# OpenLightingController.net
KiCad netlist of a schematic drawn in EasyEDA Pro
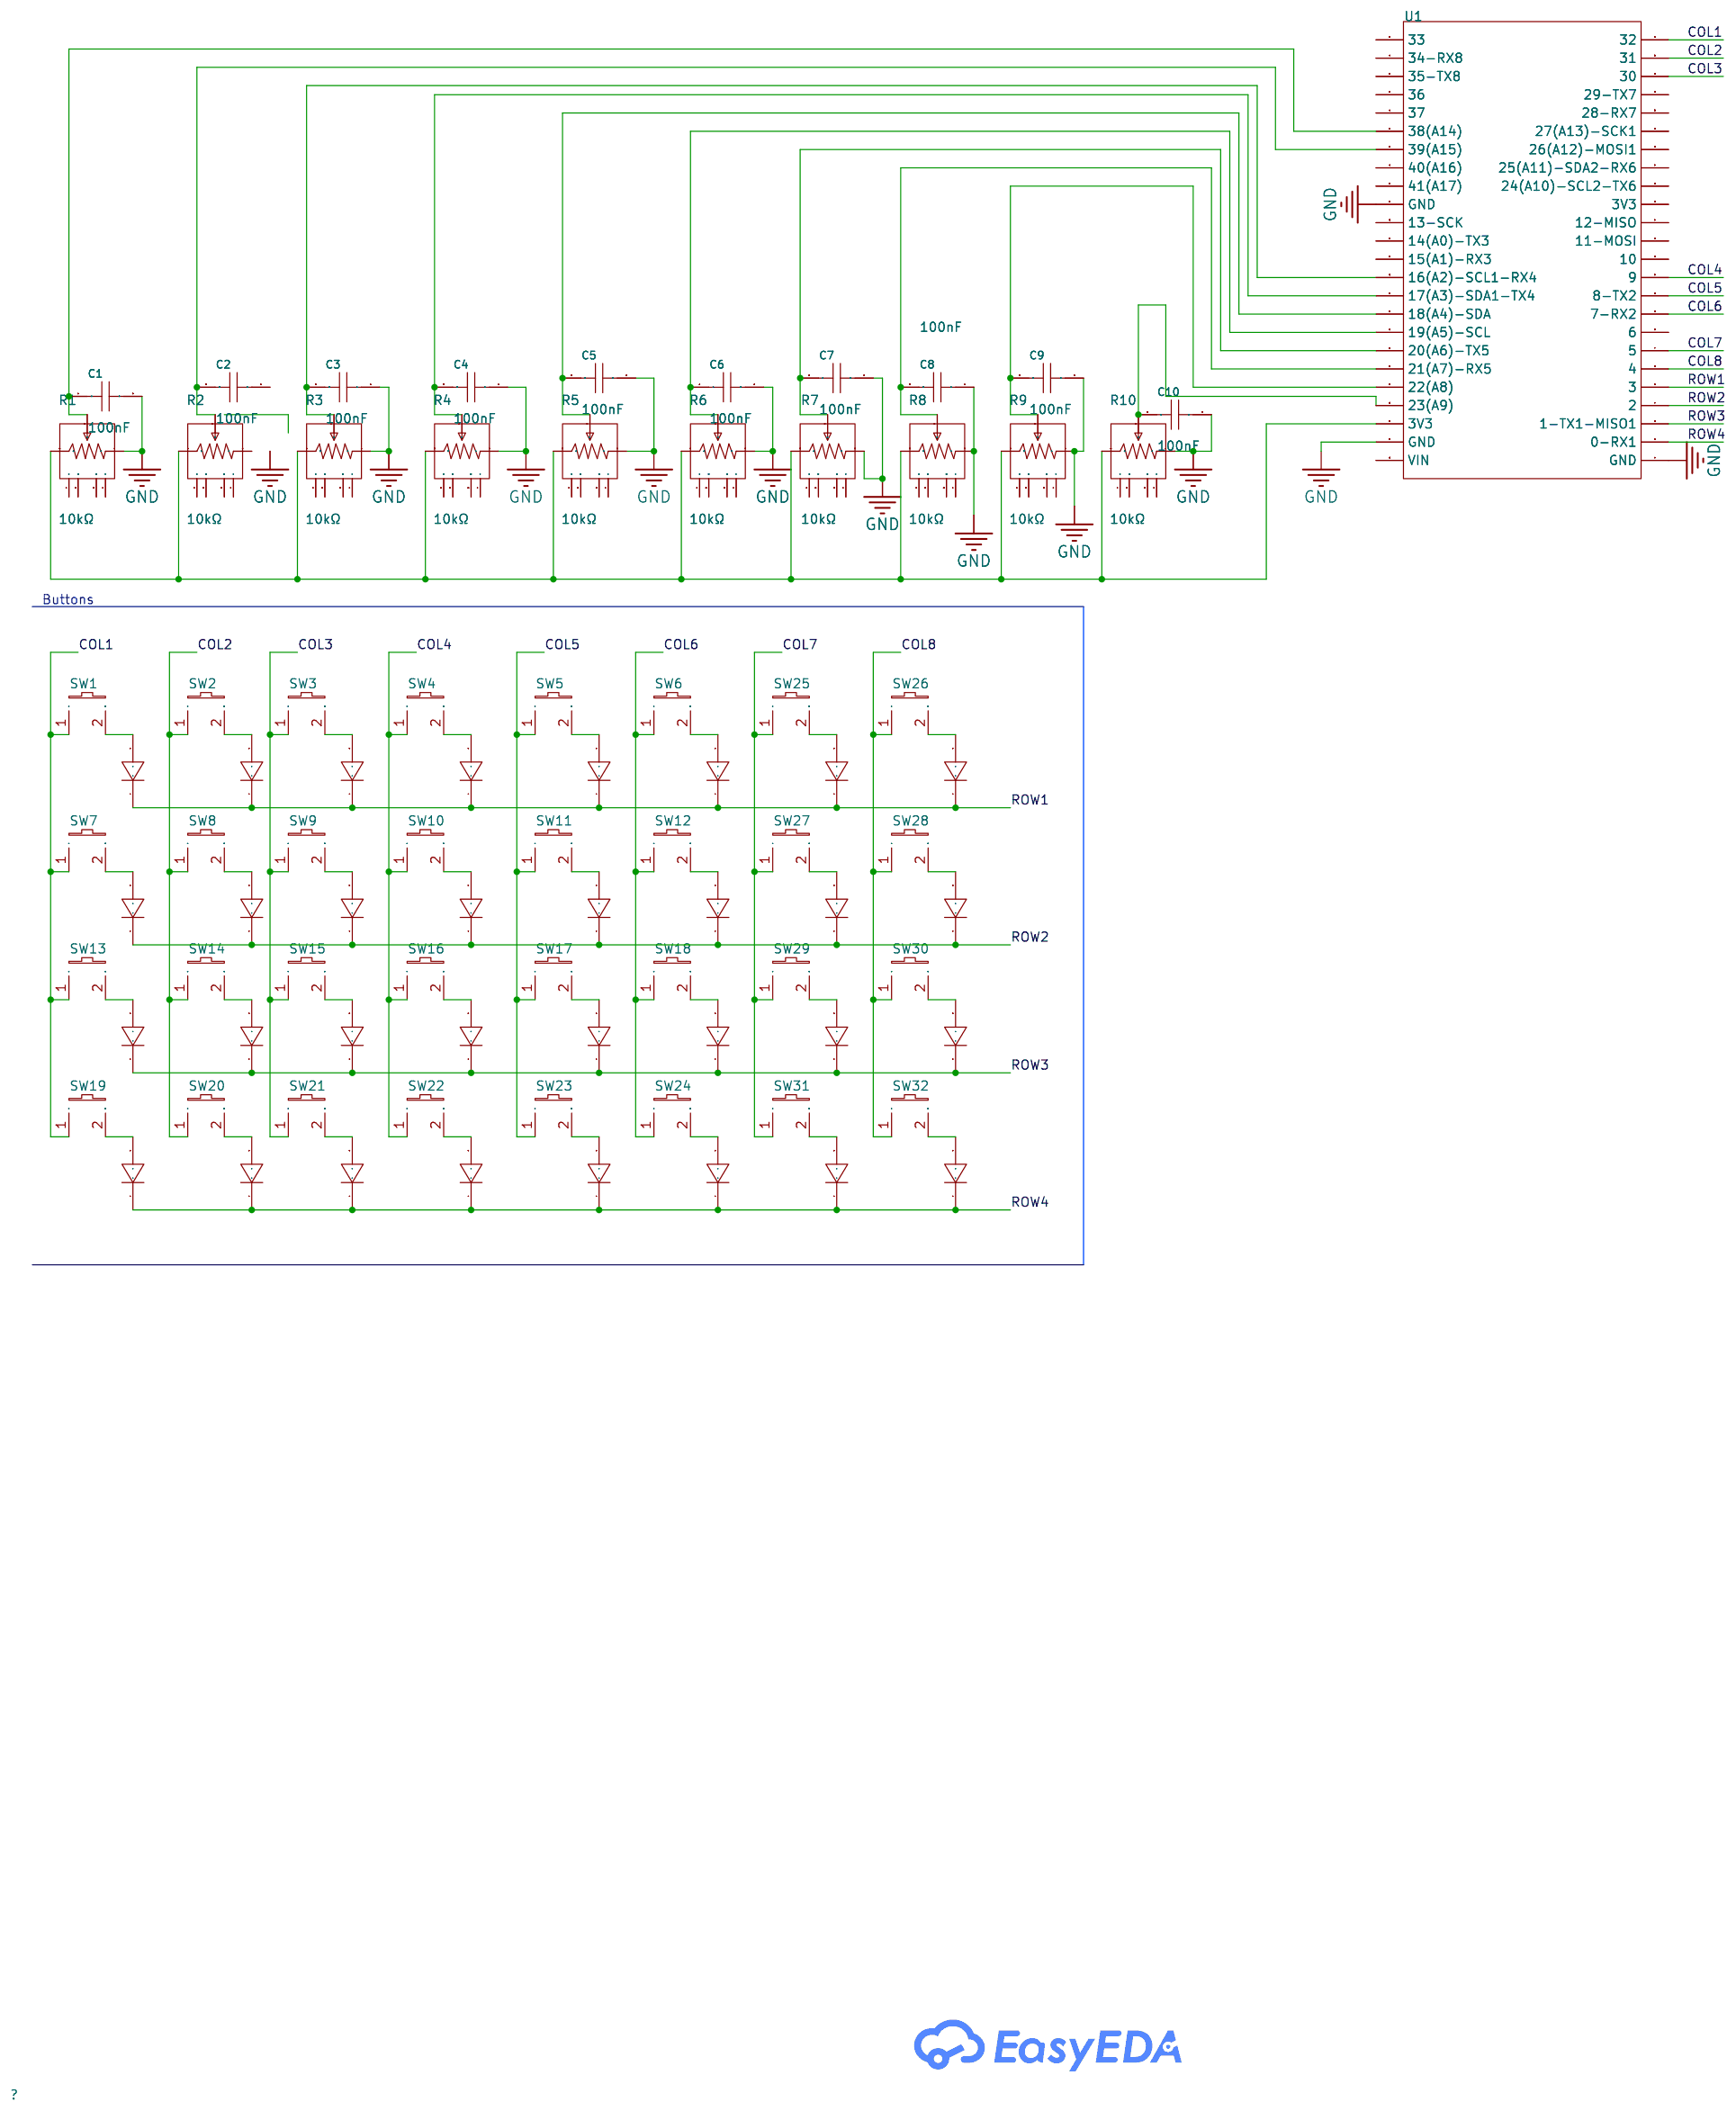
[diagram p0: schematic sheet]

(export (version "E")
  (design (tool "Eeschema 10.0.6"))
  (components
    (comp (ref "C1")
      (value "100nF")
      (fields
        (field (name "Manufacturer Part") "CC1H104ZA1ED3F5P1100")
        (field (name "Manufacturer") "Dersonic(德尔创)")
      )
      (libsource (lib "easyedapro") (part "CL10B104KB8NNNC"))
    )
    (comp (ref "C2")
      (value "100nF")
      (fields
        (field (name "Manufacturer Part") "CC1H104ZA1ED3F5P1100")
        (field (name "Manufacturer") "Dersonic(德尔创)")
      )
      (libsource (lib "easyedapro") (part "CL10B104KB8NNNC"))
    )
    (comp (ref "C3")
      (value "100nF")
      (fields
        (field (name "Manufacturer Part") "CC1H104ZA1ED3F5P1100")
        (field (name "Manufacturer") "Dersonic(德尔创)")
      )
      (libsource (lib "easyedapro") (part "CL10B104KB8NNNC"))
    )
    (comp (ref "C4")
      (value "100nF")
      (fields
        (field (name "Manufacturer Part") "CC1H104ZA1ED3F5P1100")
        (field (name "Manufacturer") "Dersonic(德尔创)")
      )
      (libsource (lib "easyedapro") (part "CL10B104KB8NNNC"))
    )
    (comp (ref "C5")
      (value "100nF")
      (fields
        (field (name "Manufacturer Part") "CC1H104ZA1ED3F5P1100")
        (field (name "Manufacturer") "Dersonic(德尔创)")
      )
      (libsource (lib "easyedapro") (part "CL10B104KB8NNNC"))
    )
    (comp (ref "C6")
      (value "100nF")
      (fields
        (field (name "Manufacturer Part") "CC1H104ZA1ED3F5P1100")
        (field (name "Manufacturer") "Dersonic(德尔创)")
      )
      (libsource (lib "easyedapro") (part "CL10B104KB8NNNC"))
    )
    (comp (ref "C7")
      (value "100nF")
      (fields
        (field (name "Manufacturer Part") "CC1H104ZA1ED3F5P1100")
        (field (name "Manufacturer") "Dersonic(德尔创)")
      )
      (libsource (lib "easyedapro") (part "CL10B104KB8NNNC"))
    )
    (comp (ref "C8")
      (value "100nF")
      (fields
        (field (name "Manufacturer Part") "CC1H104ZA1ED3F5P1100")
        (field (name "Manufacturer") "Dersonic(德尔创)")
      )
      (libsource (lib "easyedapro") (part "CL10B104KB8NNNC"))
    )
    (comp (ref "C9")
      (value "100nF")
      (fields
        (field (name "Manufacturer Part") "CC1H104ZA1ED3F5P1100")
        (field (name "Manufacturer") "Dersonic(德尔创)")
      )
      (libsource (lib "easyedapro") (part "CL10B104KB8NNNC"))
    )
    (comp (ref "C10")
      (value "100nF")
      (fields
        (field (name "Manufacturer Part") "CC1H104ZA1ED3F5P1100")
        (field (name "Manufacturer") "Dersonic(德尔创)")
      )
      (libsource (lib "easyedapro") (part "CL10B104KB8NNNC"))
    )
    (comp (ref "D1")
      (value "1N4148")
      (fields (field (name "Manufacturer") "onsemi(安森美)"))
      (libsource (lib "easyedapro") (part "1N4148W_C81598"))
    )
    (comp (ref "D2")
      (value "1N4148")
      (fields (field (name "Manufacturer") "onsemi(安森美)"))
      (libsource (lib "easyedapro") (part "1N4148W_C81598"))
    )
    (comp (ref "D3")
      (value "1N4148")
      (fields (field (name "Manufacturer") "onsemi(安森美)"))
      (libsource (lib "easyedapro") (part "1N4148W_C81598"))
    )
    (comp (ref "D4")
      (value "1N4148")
      (fields (field (name "Manufacturer") "onsemi(安森美)"))
      (libsource (lib "easyedapro") (part "1N4148W_C81598"))
    )
    (comp (ref "D5")
      (value "1N4148")
      (fields (field (name "Manufacturer") "onsemi(安森美)"))
      (libsource (lib "easyedapro") (part "1N4148W_C81598"))
    )
    (comp (ref "D6")
      (value "1N4148")
      (fields (field (name "Manufacturer") "onsemi(安森美)"))
      (libsource (lib "easyedapro") (part "1N4148W_C81598"))
    )
    (comp (ref "D7")
      (value "1N4148")
      (fields (field (name "Manufacturer") "onsemi(安森美)"))
      (libsource (lib "easyedapro") (part "1N4148W_C81598"))
    )
    (comp (ref "D8")
      (value "1N4148")
      (fields (field (name "Manufacturer") "onsemi(安森美)"))
      (libsource (lib "easyedapro") (part "1N4148W_C81598"))
    )
    (comp (ref "D9")
      (value "1N4148")
      (fields (field (name "Manufacturer") "onsemi(安森美)"))
      (libsource (lib "easyedapro") (part "1N4148W_C81598"))
    )
    (comp (ref "D10")
      (value "1N4148")
      (fields (field (name "Manufacturer") "onsemi(安森美)"))
      (libsource (lib "easyedapro") (part "1N4148W_C81598"))
    )
    (comp (ref "D11")
      (value "1N4148")
      (fields (field (name "Manufacturer") "onsemi(安森美)"))
      (libsource (lib "easyedapro") (part "1N4148W_C81598"))
    )
    (comp (ref "D12")
      (value "1N4148")
      (fields (field (name "Manufacturer") "onsemi(安森美)"))
      (libsource (lib "easyedapro") (part "1N4148W_C81598"))
    )
    (comp (ref "D13")
      (value "1N4148")
      (fields (field (name "Manufacturer") "onsemi(安森美)"))
      (libsource (lib "easyedapro") (part "1N4148W_C81598"))
    )
    (comp (ref "D14")
      (value "1N4148")
      (fields (field (name "Manufacturer") "onsemi(安森美)"))
      (libsource (lib "easyedapro") (part "1N4148W_C81598"))
    )
    (comp (ref "D15")
      (value "1N4148")
      (fields (field (name "Manufacturer") "onsemi(安森美)"))
      (libsource (lib "easyedapro") (part "1N4148W_C81598"))
    )
    (comp (ref "D16")
      (value "1N4148")
      (fields (field (name "Manufacturer") "onsemi(安森美)"))
      (libsource (lib "easyedapro") (part "1N4148W_C81598"))
    )
    (comp (ref "D17")
      (value "1N4148")
      (fields (field (name "Manufacturer") "onsemi(安森美)"))
      (libsource (lib "easyedapro") (part "1N4148W_C81598"))
    )
    (comp (ref "D18")
      (value "1N4148")
      (fields (field (name "Manufacturer") "onsemi(安森美)"))
      (libsource (lib "easyedapro") (part "1N4148W_C81598"))
    )
    (comp (ref "D19")
      (value "1N4148")
      (fields (field (name "Manufacturer") "onsemi(安森美)"))
      (libsource (lib "easyedapro") (part "1N4148W_C81598"))
    )
    (comp (ref "D20")
      (value "1N4148")
      (fields (field (name "Manufacturer") "onsemi(安森美)"))
      (libsource (lib "easyedapro") (part "1N4148W_C81598"))
    )
    (comp (ref "D21")
      (value "1N4148")
      (fields (field (name "Manufacturer") "onsemi(安森美)"))
      (libsource (lib "easyedapro") (part "1N4148W_C81598"))
    )
    (comp (ref "D22")
      (value "1N4148")
      (fields (field (name "Manufacturer") "onsemi(安森美)"))
      (libsource (lib "easyedapro") (part "1N4148W_C81598"))
    )
    (comp (ref "D23")
      (value "1N4148")
      (fields (field (name "Manufacturer") "onsemi(安森美)"))
      (libsource (lib "easyedapro") (part "1N4148W_C81598"))
    )
    (comp (ref "D24")
      (value "1N4148")
      (fields (field (name "Manufacturer") "onsemi(安森美)"))
      (libsource (lib "easyedapro") (part "1N4148W_C81598"))
    )
    (comp (ref "D25")
      (value "1N4148")
      (fields (field (name "Manufacturer") "onsemi(安森美)"))
      (libsource (lib "easyedapro") (part "1N4148W_C81598"))
    )
    (comp (ref "D26")
      (value "1N4148")
      (fields (field (name "Manufacturer") "onsemi(安森美)"))
      (libsource (lib "easyedapro") (part "1N4148W_C81598"))
    )
    (comp (ref "D27")
      (value "1N4148")
      (fields (field (name "Manufacturer") "onsemi(安森美)"))
      (libsource (lib "easyedapro") (part "1N4148W_C81598"))
    )
    (comp (ref "D28")
      (value "1N4148")
      (fields (field (name "Manufacturer") "onsemi(安森美)"))
      (libsource (lib "easyedapro") (part "1N4148W_C81598"))
    )
    (comp (ref "D29")
      (value "1N4148")
      (fields (field (name "Manufacturer") "onsemi(安森美)"))
      (libsource (lib "easyedapro") (part "1N4148W_C81598"))
    )
    (comp (ref "D30")
      (value "1N4148")
      (fields (field (name "Manufacturer") "onsemi(安森美)"))
      (libsource (lib "easyedapro") (part "1N4148W_C81598"))
    )
    (comp (ref "D31")
      (value "1N4148")
      (fields (field (name "Manufacturer") "onsemi(安森美)"))
      (libsource (lib "easyedapro") (part "1N4148W_C81598"))
    )
    (comp (ref "D32")
      (value "1N4148")
      (fields (field (name "Manufacturer") "onsemi(安森美)"))
      (libsource (lib "easyedapro") (part "1N4148W_C81598"))
    )
    (comp (ref "R1")
      (value "10kΩ")
      (footprint "easyedapro:RES-ADJ-TH_PTA6043-2015DPB103")
      (description "Resistance:10kΩ Tolerance:±20% Tolerance:±20% Voltage Rating:200V Power(Watts):250mW")
      (fields (field (name "Manufacturer Part") "PTA6043-2015CPB103") (field (name "Manufacturer") "BOURNS"))
      (libsource (lib "easyedapro") (part "PTA6043-2015CPB103"))
    )
    (comp (ref "R2")
      (value "10kΩ")
      (footprint "easyedapro:RES-ADJ-TH_PTA6043-2015DPB103")
      (description "Resistance:10kΩ Tolerance:±20% Tolerance:±20% Voltage Rating:200V Power(Watts):250mW")
      (fields (field (name "Manufacturer Part") "PTA6043-2015CPB103") (field (name "Manufacturer") "BOURNS"))
      (libsource (lib "easyedapro") (part "PTA6043-2015CPB103"))
    )
    (comp (ref "R3")
      (value "10kΩ")
      (footprint "easyedapro:RES-ADJ-TH_PTA6043-2015DPB103")
      (description "Resistance:10kΩ Tolerance:±20% Tolerance:±20% Voltage Rating:200V Power(Watts):250mW")
      (fields (field (name "Manufacturer Part") "PTA6043-2015CPB103") (field (name "Manufacturer") "BOURNS"))
      (libsource (lib "easyedapro") (part "PTA6043-2015CPB103"))
    )
    (comp (ref "R4")
      (value "10kΩ")
      (footprint "easyedapro:RES-ADJ-TH_PTA6043-2015DPB103")
      (description "Resistance:10kΩ Tolerance:±20% Tolerance:±20% Voltage Rating:200V Power(Watts):250mW")
      (fields (field (name "Manufacturer Part") "PTA6043-2015CPB103") (field (name "Manufacturer") "BOURNS"))
      (libsource (lib "easyedapro") (part "PTA6043-2015CPB103"))
    )
    (comp (ref "R5")
      (value "10kΩ")
      (footprint "easyedapro:RES-ADJ-TH_PTA6043-2015DPB103")
      (description "Resistance:10kΩ Tolerance:±20% Tolerance:±20% Voltage Rating:200V Power(Watts):250mW")
      (fields (field (name "Manufacturer Part") "PTA6043-2015CPB103") (field (name "Manufacturer") "BOURNS"))
      (libsource (lib "easyedapro") (part "PTA6043-2015CPB103"))
    )
    (comp (ref "R6")
      (value "10kΩ")
      (footprint "easyedapro:RES-ADJ-TH_PTA6043-2015DPB103")
      (description "Resistance:10kΩ Tolerance:±20% Tolerance:±20% Voltage Rating:200V Power(Watts):250mW")
      (fields (field (name "Manufacturer Part") "PTA6043-2015CPB103") (field (name "Manufacturer") "BOURNS"))
      (libsource (lib "easyedapro") (part "PTA6043-2015CPB103"))
    )
    (comp (ref "R7")
      (value "10kΩ")
      (footprint "easyedapro:RES-ADJ-TH_PTA6043-2015DPB103")
      (description "Resistance:10kΩ Tolerance:±20% Tolerance:±20% Voltage Rating:200V Power(Watts):250mW")
      (fields (field (name "Manufacturer Part") "PTA6043-2015CPB103") (field (name "Manufacturer") "BOURNS"))
      (libsource (lib "easyedapro") (part "PTA6043-2015CPB103"))
    )
    (comp (ref "R8")
      (value "10kΩ")
      (footprint "easyedapro:RES-ADJ-TH_PTA6043-2015DPB103")
      (description "Resistance:10kΩ Tolerance:±20% Tolerance:±20% Voltage Rating:200V Power(Watts):250mW")
      (fields (field (name "Manufacturer Part") "PTA6043-2015CPB103") (field (name "Manufacturer") "BOURNS"))
      (libsource (lib "easyedapro") (part "PTA6043-2015CPB103"))
    )
    (comp (ref "R9")
      (value "10kΩ")
      (footprint "easyedapro:RES-ADJ-TH_PTA6043-2015DPB103")
      (description "Resistance:10kΩ Tolerance:±20% Tolerance:±20% Voltage Rating:200V Power(Watts):250mW")
      (fields (field (name "Manufacturer Part") "PTA6043-2015CPB103") (field (name "Manufacturer") "BOURNS"))
      (libsource (lib "easyedapro") (part "PTA6043-2015CPB103"))
    )
    (comp (ref "R10")
      (value "10kΩ")
      (footprint "easyedapro:RES-ADJ-TH_PTA6043-2015DPB103")
      (description "Resistance:10kΩ Tolerance:±20% Tolerance:±20% Voltage Rating:200V Power(Watts):250mW")
      (fields (field (name "Manufacturer Part") "PTA6043-2015CPB103") (field (name "Manufacturer") "BOURNS"))
      (libsource (lib "easyedapro") (part "PTA6043-2015CPB103"))
    )
    (comp (ref "SW1")
      (value "MX Switch")
      (footprint "easyedapro:SW-TH_MX1A-11NW")
      (fields (field (name "Manufacturer Part") "MX1A-11NW") (field (name "Manufacturer") "CHERRY"))
      (libsource (lib "easyedapro") (part "MX1A-11NW"))
    )
    (comp (ref "SW2")
      (value "MX Switch")
      (footprint "easyedapro:SW-TH_MX1A-11NW")
      (fields (field (name "Manufacturer Part") "MX1A-11NW") (field (name "Manufacturer") "CHERRY"))
      (libsource (lib "easyedapro") (part "MX1A-11NW"))
    )
    (comp (ref "SW3")
      (value "MX Switch")
      (footprint "easyedapro:SW-TH_MX1A-11NW")
      (fields (field (name "Manufacturer Part") "MX1A-11NW") (field (name "Manufacturer") "CHERRY"))
      (libsource (lib "easyedapro") (part "MX1A-11NW"))
    )
    (comp (ref "SW4")
      (value "MX Switch")
      (footprint "easyedapro:SW-TH_MX1A-11NW")
      (fields (field (name "Manufacturer Part") "MX1A-11NW") (field (name "Manufacturer") "CHERRY"))
      (libsource (lib "easyedapro") (part "MX1A-11NW"))
    )
    (comp (ref "SW5")
      (value "MX Switch")
      (footprint "easyedapro:SW-TH_MX1A-11NW")
      (fields (field (name "Manufacturer Part") "MX1A-11NW") (field (name "Manufacturer") "CHERRY"))
      (libsource (lib "easyedapro") (part "MX1A-11NW"))
    )
    (comp (ref "SW6")
      (value "MX Switch")
      (footprint "easyedapro:SW-TH_MX1A-11NW")
      (fields (field (name "Manufacturer Part") "MX1A-11NW") (field (name "Manufacturer") "CHERRY"))
      (libsource (lib "easyedapro") (part "MX1A-11NW"))
    )
    (comp (ref "SW7")
      (value "MX Switch")
      (footprint "easyedapro:SW-TH_MX1A-11NW")
      (fields (field (name "Manufacturer Part") "MX1A-11NW") (field (name "Manufacturer") "CHERRY"))
      (libsource (lib "easyedapro") (part "MX1A-11NW"))
    )
    (comp (ref "SW8")
      (value "MX Switch")
      (footprint "easyedapro:SW-TH_MX1A-11NW")
      (fields (field (name "Manufacturer Part") "MX1A-11NW") (field (name "Manufacturer") "CHERRY"))
      (libsource (lib "easyedapro") (part "MX1A-11NW"))
    )
    (comp (ref "SW9")
      (value "MX Switch")
      (footprint "easyedapro:SW-TH_MX1A-11NW")
      (fields (field (name "Manufacturer Part") "MX1A-11NW") (field (name "Manufacturer") "CHERRY"))
      (libsource (lib "easyedapro") (part "MX1A-11NW"))
    )
    (comp (ref "SW10")
      (value "MX Switch")
      (footprint "easyedapro:SW-TH_MX1A-11NW")
      (fields (field (name "Manufacturer Part") "MX1A-11NW") (field (name "Manufacturer") "CHERRY"))
      (libsource (lib "easyedapro") (part "MX1A-11NW"))
    )
    (comp (ref "SW11")
      (value "MX Switch")
      (footprint "easyedapro:SW-TH_MX1A-11NW")
      (fields (field (name "Manufacturer Part") "MX1A-11NW") (field (name "Manufacturer") "CHERRY"))
      (libsource (lib "easyedapro") (part "MX1A-11NW"))
    )
    (comp (ref "SW12")
      (value "MX Switch")
      (footprint "easyedapro:SW-TH_MX1A-11NW")
      (fields (field (name "Manufacturer Part") "MX1A-11NW") (field (name "Manufacturer") "CHERRY"))
      (libsource (lib "easyedapro") (part "MX1A-11NW"))
    )
    (comp (ref "SW13")
      (value "MX Switch")
      (footprint "easyedapro:SW-TH_MX1A-11NW")
      (fields (field (name "Manufacturer Part") "MX1A-11NW") (field (name "Manufacturer") "CHERRY"))
      (libsource (lib "easyedapro") (part "MX1A-11NW"))
    )
    (comp (ref "SW14")
      (value "MX Switch")
      (footprint "easyedapro:SW-TH_MX1A-11NW")
      (fields (field (name "Manufacturer Part") "MX1A-11NW") (field (name "Manufacturer") "CHERRY"))
      (libsource (lib "easyedapro") (part "MX1A-11NW"))
    )
    (comp (ref "SW15")
      (value "MX Switch")
      (footprint "easyedapro:SW-TH_MX1A-11NW")
      (fields (field (name "Manufacturer Part") "MX1A-11NW") (field (name "Manufacturer") "CHERRY"))
      (libsource (lib "easyedapro") (part "MX1A-11NW"))
    )
    (comp (ref "SW16")
      (value "MX Switch")
      (footprint "easyedapro:SW-TH_MX1A-11NW")
      (fields (field (name "Manufacturer Part") "MX1A-11NW") (field (name "Manufacturer") "CHERRY"))
      (libsource (lib "easyedapro") (part "MX1A-11NW"))
    )
    (comp (ref "SW17")
      (value "MX Switch")
      (footprint "easyedapro:SW-TH_MX1A-11NW")
      (fields (field (name "Manufacturer Part") "MX1A-11NW") (field (name "Manufacturer") "CHERRY"))
      (libsource (lib "easyedapro") (part "MX1A-11NW"))
    )
    (comp (ref "SW18")
      (value "MX Switch")
      (footprint "easyedapro:SW-TH_MX1A-11NW")
      (fields (field (name "Manufacturer Part") "MX1A-11NW") (field (name "Manufacturer") "CHERRY"))
      (libsource (lib "easyedapro") (part "MX1A-11NW"))
    )
    (comp (ref "SW19")
      (value "MX Switch")
      (footprint "easyedapro:SW-TH_MX1A-11NW")
      (fields (field (name "Manufacturer Part") "MX1A-11NW") (field (name "Manufacturer") "CHERRY"))
      (libsource (lib "easyedapro") (part "MX1A-11NW"))
    )
    (comp (ref "SW20")
      (value "MX Switch")
      (footprint "easyedapro:SW-TH_MX1A-11NW")
      (fields (field (name "Manufacturer Part") "MX1A-11NW") (field (name "Manufacturer") "CHERRY"))
      (libsource (lib "easyedapro") (part "MX1A-11NW"))
    )
    (comp (ref "SW21")
      (value "MX Switch")
      (footprint "easyedapro:SW-TH_MX1A-11NW")
      (fields (field (name "Manufacturer Part") "MX1A-11NW") (field (name "Manufacturer") "CHERRY"))
      (libsource (lib "easyedapro") (part "MX1A-11NW"))
    )
    (comp (ref "SW22")
      (value "MX Switch")
      (footprint "easyedapro:SW-TH_MX1A-11NW")
      (fields (field (name "Manufacturer Part") "MX1A-11NW") (field (name "Manufacturer") "CHERRY"))
      (libsource (lib "easyedapro") (part "MX1A-11NW"))
    )
    (comp (ref "SW23")
      (value "MX Switch")
      (footprint "easyedapro:SW-TH_MX1A-11NW")
      (fields (field (name "Manufacturer Part") "MX1A-11NW") (field (name "Manufacturer") "CHERRY"))
      (libsource (lib "easyedapro") (part "MX1A-11NW"))
    )
    (comp (ref "SW24")
      (value "MX Switch")
      (footprint "easyedapro:SW-TH_MX1A-11NW")
      (fields (field (name "Manufacturer Part") "MX1A-11NW") (field (name "Manufacturer") "CHERRY"))
      (libsource (lib "easyedapro") (part "MX1A-11NW"))
    )
    (comp (ref "SW25")
      (value "MX Switch")
      (footprint "easyedapro:SW-TH_MX1A-11NW")
      (fields (field (name "Manufacturer Part") "MX1A-11NW") (field (name "Manufacturer") "CHERRY"))
      (libsource (lib "easyedapro") (part "MX1A-11NW"))
    )
    (comp (ref "SW26")
      (value "MX Switch")
      (footprint "easyedapro:SW-TH_MX1A-11NW")
      (fields (field (name "Manufacturer Part") "MX1A-11NW") (field (name "Manufacturer") "CHERRY"))
      (libsource (lib "easyedapro") (part "MX1A-11NW"))
    )
    (comp (ref "SW27")
      (value "MX Switch")
      (footprint "easyedapro:SW-TH_MX1A-11NW")
      (fields (field (name "Manufacturer Part") "MX1A-11NW") (field (name "Manufacturer") "CHERRY"))
      (libsource (lib "easyedapro") (part "MX1A-11NW"))
    )
    (comp (ref "SW28")
      (value "MX Switch")
      (footprint "easyedapro:SW-TH_MX1A-11NW")
      (fields (field (name "Manufacturer Part") "MX1A-11NW") (field (name "Manufacturer") "CHERRY"))
      (libsource (lib "easyedapro") (part "MX1A-11NW"))
    )
    (comp (ref "SW29")
      (value "MX Switch")
      (footprint "easyedapro:SW-TH_MX1A-11NW")
      (fields (field (name "Manufacturer Part") "MX1A-11NW") (field (name "Manufacturer") "CHERRY"))
      (libsource (lib "easyedapro") (part "MX1A-11NW"))
    )
    (comp (ref "SW30")
      (value "MX Switch")
      (footprint "easyedapro:SW-TH_MX1A-11NW")
      (fields (field (name "Manufacturer Part") "MX1A-11NW") (field (name "Manufacturer") "CHERRY"))
      (libsource (lib "easyedapro") (part "MX1A-11NW"))
    )
    (comp (ref "SW31")
      (value "MX Switch")
      (footprint "easyedapro:SW-TH_MX1A-11NW")
      (fields (field (name "Manufacturer Part") "MX1A-11NW") (field (name "Manufacturer") "CHERRY"))
      (libsource (lib "easyedapro") (part "MX1A-11NW"))
    )
    (comp (ref "SW32")
      (value "MX Switch")
      (footprint "easyedapro:SW-TH_MX1A-11NW")
      (fields (field (name "Manufacturer Part") "MX1A-11NW") (field (name "Manufacturer") "CHERRY"))
      (libsource (lib "easyedapro") (part "MX1A-11NW"))
    )
    (comp (ref "U1")
      (value "~")
      (footprint "easyedapro:teensy 4.1")
      (libsource (lib "easyedapro") (part "teensy 4.1"))
    )
  )
  (nets
    (net (code "1") (name "/COL1") (class "Default")
      (node (ref "SW1") (pin "1") (pinfunction "1_1") (pintype "unspecified"))
      (node (ref "SW13") (pin "1") (pinfunction "1_1") (pintype "unspecified"))
      (node (ref "SW19") (pin "1") (pinfunction "1_1") (pintype "unspecified"))
      (node (ref "SW7") (pin "1") (pinfunction "1_1") (pintype "unspecified"))
      (node (ref "U1") (pin "24") (pinfunction "32_24") (pintype "input"))
    )
    (net (code "2") (name "/COL2") (class "Default")
      (node (ref "SW14") (pin "1") (pinfunction "1_1") (pintype "unspecified"))
      (node (ref "SW2") (pin "1") (pinfunction "1_1") (pintype "unspecified"))
      (node (ref "SW20") (pin "1") (pinfunction "1_1") (pintype "unspecified"))
      (node (ref "SW8") (pin "1") (pinfunction "1_1") (pintype "unspecified"))
      (node (ref "U1") (pin "23") (pinfunction "31_23") (pintype "input"))
    )
    (net (code "3") (name "/COL3") (class "Default")
      (node (ref "SW15") (pin "1") (pinfunction "1_1") (pintype "unspecified"))
      (node (ref "SW21") (pin "1") (pinfunction "1_1") (pintype "unspecified"))
      (node (ref "SW3") (pin "1") (pinfunction "1_1") (pintype "unspecified"))
      (node (ref "SW9") (pin "1") (pinfunction "1_1") (pintype "unspecified"))
      (node (ref "U1") (pin "22") (pinfunction "30_22") (pintype "input"))
    )
    (net (code "4") (name "/COL4") (class "Default")
      (node (ref "SW10") (pin "1") (pinfunction "1_1") (pintype "unspecified"))
      (node (ref "SW16") (pin "1") (pinfunction "1_1") (pintype "unspecified"))
      (node (ref "SW22") (pin "1") (pinfunction "1_1") (pintype "unspecified"))
      (node (ref "SW4") (pin "1") (pinfunction "1_1") (pintype "unspecified"))
      (node (ref "U1") (pin "11") (pinfunction "9_11") (pintype "input"))
    )
    (net (code "5") (name "/COL5") (class "Default")
      (node (ref "SW11") (pin "1") (pinfunction "1_1") (pintype "unspecified"))
      (node (ref "SW17") (pin "1") (pinfunction "1_1") (pintype "unspecified"))
      (node (ref "SW23") (pin "1") (pinfunction "1_1") (pintype "unspecified"))
      (node (ref "SW5") (pin "1") (pinfunction "1_1") (pintype "unspecified"))
      (node (ref "U1") (pin "10") (pinfunction "8-TX2_10") (pintype "input"))
    )
    (net (code "6") (name "/COL6") (class "Default")
      (node (ref "SW12") (pin "1") (pinfunction "1_1") (pintype "unspecified"))
      (node (ref "SW18") (pin "1") (pinfunction "1_1") (pintype "unspecified"))
      (node (ref "SW24") (pin "1") (pinfunction "1_1") (pintype "unspecified"))
      (node (ref "SW6") (pin "1") (pinfunction "1_1") (pintype "unspecified"))
      (node (ref "U1") (pin "9") (pinfunction "7-RX2_9") (pintype "input"))
    )
    (net (code "7") (name "/COL7") (class "Default")
      (node (ref "SW25") (pin "1") (pinfunction "1_1") (pintype "unspecified"))
      (node (ref "SW27") (pin "1") (pinfunction "1_1") (pintype "unspecified"))
      (node (ref "SW29") (pin "1") (pinfunction "1_1") (pintype "unspecified"))
      (node (ref "SW31") (pin "1") (pinfunction "1_1") (pintype "unspecified"))
      (node (ref "U1") (pin "7") (pinfunction "5_7") (pintype "input"))
    )
    (net (code "8") (name "/COL8") (class "Default")
      (node (ref "SW26") (pin "1") (pinfunction "1_1") (pintype "unspecified"))
      (node (ref "SW28") (pin "1") (pinfunction "1_1") (pintype "unspecified"))
      (node (ref "SW30") (pin "1") (pinfunction "1_1") (pintype "unspecified"))
      (node (ref "SW32") (pin "1") (pinfunction "1_1") (pintype "unspecified"))
      (node (ref "U1") (pin "6") (pinfunction "4_6") (pintype "input"))
    )
    (net (code "9") (name "/ROW1") (class "Default")
      (node (ref "D1") (pin "1") (pinfunction "K_1") (pintype "unspecified"))
      (node (ref "D2") (pin "1") (pinfunction "K_1") (pintype "unspecified"))
      (node (ref "D25") (pin "1") (pinfunction "K_1") (pintype "unspecified"))
      (node (ref "D26") (pin "1") (pinfunction "K_1") (pintype "unspecified"))
      (node (ref "D3") (pin "1") (pinfunction "K_1") (pintype "unspecified"))
      (node (ref "D4") (pin "1") (pinfunction "K_1") (pintype "unspecified"))
      (node (ref "D5") (pin "1") (pinfunction "K_1") (pintype "unspecified"))
      (node (ref "D6") (pin "1") (pinfunction "K_1") (pintype "unspecified"))
      (node (ref "U1") (pin "5") (pinfunction "3_5") (pintype "input"))
    )
    (net (code "10") (name "/ROW2") (class "Default")
      (node (ref "D10") (pin "1") (pinfunction "K_1") (pintype "unspecified"))
      (node (ref "D11") (pin "1") (pinfunction "K_1") (pintype "unspecified"))
      (node (ref "D12") (pin "1") (pinfunction "K_1") (pintype "unspecified"))
      (node (ref "D27") (pin "1") (pinfunction "K_1") (pintype "unspecified"))
      (node (ref "D28") (pin "1") (pinfunction "K_1") (pintype "unspecified"))
      (node (ref "D7") (pin "1") (pinfunction "K_1") (pintype "unspecified"))
      (node (ref "D8") (pin "1") (pinfunction "K_1") (pintype "unspecified"))
      (node (ref "D9") (pin "1") (pinfunction "K_1") (pintype "unspecified"))
      (node (ref "U1") (pin "4") (pinfunction "2_4") (pintype "input"))
    )
    (net (code "11") (name "/ROW3") (class "Default")
      (node (ref "D13") (pin "1") (pinfunction "K_1") (pintype "unspecified"))
      (node (ref "D14") (pin "1") (pinfunction "K_1") (pintype "unspecified"))
      (node (ref "D15") (pin "1") (pinfunction "K_1") (pintype "unspecified"))
      (node (ref "D16") (pin "1") (pinfunction "K_1") (pintype "unspecified"))
      (node (ref "D17") (pin "1") (pinfunction "K_1") (pintype "unspecified"))
      (node (ref "D18") (pin "1") (pinfunction "K_1") (pintype "unspecified"))
      (node (ref "D29") (pin "1") (pinfunction "K_1") (pintype "unspecified"))
      (node (ref "D30") (pin "1") (pinfunction "K_1") (pintype "unspecified"))
      (node (ref "U1") (pin "3") (pinfunction "1-TX1-MISO1_3") (pintype "input"))
    )
    (net (code "12") (name "/ROW4") (class "Default")
      (node (ref "D19") (pin "1") (pinfunction "K_1") (pintype "unspecified"))
      (node (ref "D20") (pin "1") (pinfunction "K_1") (pintype "unspecified"))
      (node (ref "D21") (pin "1") (pinfunction "K_1") (pintype "unspecified"))
      (node (ref "D22") (pin "1") (pinfunction "K_1") (pintype "unspecified"))
      (node (ref "D23") (pin "1") (pinfunction "K_1") (pintype "unspecified"))
      (node (ref "D24") (pin "1") (pinfunction "K_1") (pintype "unspecified"))
      (node (ref "D31") (pin "1") (pinfunction "K_1") (pintype "unspecified"))
      (node (ref "D32") (pin "1") (pinfunction "K_1") (pintype "unspecified"))
      (node (ref "U1") (pin "2") (pinfunction "0-RX1_2") (pintype "input"))
    )
    (net (code "13") (name "GND") (class "Default")
      (node (ref "C1") (pin "2") (pinfunction "2_2") (pintype "input"))
      (node (ref "C10") (pin "1") (pinfunction "1_1") (pintype "input"))
      (node (ref "C3") (pin "1") (pinfunction "1_1") (pintype "input"))
      (node (ref "C4") (pin "1") (pinfunction "1_1") (pintype "input"))
      (node (ref "C5") (pin "1") (pinfunction "1_1") (pintype "input"))
      (node (ref "C6") (pin "2") (pinfunction "2_2") (pintype "input"))
      (node (ref "C7") (pin "1") (pinfunction "1_1") (pintype "input"))
      (node (ref "C8") (pin "1") (pinfunction "1_1") (pintype "input"))
      (node (ref "C9") (pin "1") (pinfunction "1_1") (pintype "input"))
      (node (ref "R1") (pin "1") (pinfunction "1_1") (pintype "unspecified"))
      (node (ref "R10") (pin "1") (pinfunction "1_1") (pintype "unspecified"))
      (node (ref "R3") (pin "1") (pinfunction "1_1") (pintype "unspecified"))
      (node (ref "R4") (pin "1") (pinfunction "1_1") (pintype "unspecified"))
      (node (ref "R5") (pin "1") (pinfunction "1_1") (pintype "unspecified"))
      (node (ref "R6") (pin "1") (pinfunction "1_1") (pintype "unspecified"))
      (node (ref "R7") (pin "1") (pinfunction "1_1") (pintype "unspecified"))
      (node (ref "R8") (pin "1") (pinfunction "1_1") (pintype "unspecified"))
      (node (ref "R9") (pin "1") (pinfunction "1_1") (pintype "unspecified"))
      (node (ref "U1") (pin "1") (pinfunction "GND_1") (pintype "input"))
      (node (ref "U1") (pin "26") (pinfunction "GND_26") (pintype "input"))
      (node (ref "U1") (pin "39") (pinfunction "GND_39") (pintype "input"))
    )
    (net (code "14") (name "Net-(D1-A)") (class "Default")
      (node (ref "D1") (pin "2") (pinfunction "A_2") (pintype "unspecified"))
      (node (ref "SW1") (pin "2") (pinfunction "2_2") (pintype "unspecified"))
    )
    (net (code "15") (name "Net-(D2-A)") (class "Default")
      (node (ref "D2") (pin "2") (pinfunction "A_2") (pintype "unspecified"))
      (node (ref "SW2") (pin "2") (pinfunction "2_2") (pintype "unspecified"))
    )
    (net (code "16") (name "Net-(D3-A)") (class "Default")
      (node (ref "D3") (pin "2") (pinfunction "A_2") (pintype "unspecified"))
      (node (ref "SW3") (pin "2") (pinfunction "2_2") (pintype "unspecified"))
    )
    (net (code "17") (name "Net-(D4-A)") (class "Default")
      (node (ref "D4") (pin "2") (pinfunction "A_2") (pintype "unspecified"))
      (node (ref "SW4") (pin "2") (pinfunction "2_2") (pintype "unspecified"))
    )
    (net (code "18") (name "Net-(D5-A)") (class "Default")
      (node (ref "D5") (pin "2") (pinfunction "A_2") (pintype "unspecified"))
      (node (ref "SW5") (pin "2") (pinfunction "2_2") (pintype "unspecified"))
    )
    (net (code "19") (name "Net-(D6-A)") (class "Default")
      (node (ref "D6") (pin "2") (pinfunction "A_2") (pintype "unspecified"))
      (node (ref "SW6") (pin "2") (pinfunction "2_2") (pintype "unspecified"))
    )
    (net (code "20") (name "Net-(D7-A)") (class "Default")
      (node (ref "D7") (pin "2") (pinfunction "A_2") (pintype "unspecified"))
      (node (ref "SW7") (pin "2") (pinfunction "2_2") (pintype "unspecified"))
    )
    (net (code "21") (name "Net-(D8-A)") (class "Default")
      (node (ref "D8") (pin "2") (pinfunction "A_2") (pintype "unspecified"))
      (node (ref "SW8") (pin "2") (pinfunction "2_2") (pintype "unspecified"))
    )
    (net (code "22") (name "Net-(D9-A)") (class "Default")
      (node (ref "D9") (pin "2") (pinfunction "A_2") (pintype "unspecified"))
      (node (ref "SW9") (pin "2") (pinfunction "2_2") (pintype "unspecified"))
    )
    (net (code "23") (name "Net-(D10-A)") (class "Default")
      (node (ref "D10") (pin "2") (pinfunction "A_2") (pintype "unspecified"))
      (node (ref "SW10") (pin "2") (pinfunction "2_2") (pintype "unspecified"))
    )
    (net (code "24") (name "Net-(D11-A)") (class "Default")
      (node (ref "D11") (pin "2") (pinfunction "A_2") (pintype "unspecified"))
      (node (ref "SW11") (pin "2") (pinfunction "2_2") (pintype "unspecified"))
    )
    (net (code "25") (name "Net-(D12-A)") (class "Default")
      (node (ref "D12") (pin "2") (pinfunction "A_2") (pintype "unspecified"))
      (node (ref "SW12") (pin "2") (pinfunction "2_2") (pintype "unspecified"))
    )
    (net (code "26") (name "Net-(D13-A)") (class "Default")
      (node (ref "D13") (pin "2") (pinfunction "A_2") (pintype "unspecified"))
      (node (ref "SW13") (pin "2") (pinfunction "2_2") (pintype "unspecified"))
    )
    (net (code "27") (name "Net-(D14-A)") (class "Default")
      (node (ref "D14") (pin "2") (pinfunction "A_2") (pintype "unspecified"))
      (node (ref "SW14") (pin "2") (pinfunction "2_2") (pintype "unspecified"))
    )
    (net (code "28") (name "Net-(D15-A)") (class "Default")
      (node (ref "D15") (pin "2") (pinfunction "A_2") (pintype "unspecified"))
      (node (ref "SW15") (pin "2") (pinfunction "2_2") (pintype "unspecified"))
    )
    (net (code "29") (name "Net-(D16-A)") (class "Default")
      (node (ref "D16") (pin "2") (pinfunction "A_2") (pintype "unspecified"))
      (node (ref "SW16") (pin "2") (pinfunction "2_2") (pintype "unspecified"))
    )
    (net (code "30") (name "Net-(D17-A)") (class "Default")
      (node (ref "D17") (pin "2") (pinfunction "A_2") (pintype "unspecified"))
      (node (ref "SW17") (pin "2") (pinfunction "2_2") (pintype "unspecified"))
    )
    (net (code "31") (name "Net-(D18-A)") (class "Default")
      (node (ref "D18") (pin "2") (pinfunction "A_2") (pintype "unspecified"))
      (node (ref "SW18") (pin "2") (pinfunction "2_2") (pintype "unspecified"))
    )
    (net (code "32") (name "Net-(D19-A)") (class "Default")
      (node (ref "D19") (pin "2") (pinfunction "A_2") (pintype "unspecified"))
      (node (ref "SW19") (pin "2") (pinfunction "2_2") (pintype "unspecified"))
    )
    (net (code "33") (name "Net-(D20-A)") (class "Default")
      (node (ref "D20") (pin "2") (pinfunction "A_2") (pintype "unspecified"))
      (node (ref "SW20") (pin "2") (pinfunction "2_2") (pintype "unspecified"))
    )
    (net (code "34") (name "Net-(D21-A)") (class "Default")
      (node (ref "D21") (pin "2") (pinfunction "A_2") (pintype "unspecified"))
      (node (ref "SW21") (pin "2") (pinfunction "2_2") (pintype "unspecified"))
    )
    (net (code "35") (name "Net-(D22-A)") (class "Default")
      (node (ref "D22") (pin "2") (pinfunction "A_2") (pintype "unspecified"))
      (node (ref "SW22") (pin "2") (pinfunction "2_2") (pintype "unspecified"))
    )
    (net (code "36") (name "Net-(D23-A)") (class "Default")
      (node (ref "D23") (pin "2") (pinfunction "A_2") (pintype "unspecified"))
      (node (ref "SW23") (pin "2") (pinfunction "2_2") (pintype "unspecified"))
    )
    (net (code "37") (name "Net-(D24-A)") (class "Default")
      (node (ref "D24") (pin "2") (pinfunction "A_2") (pintype "unspecified"))
      (node (ref "SW24") (pin "2") (pinfunction "2_2") (pintype "unspecified"))
    )
    (net (code "38") (name "Net-(D25-A)") (class "Default")
      (node (ref "D25") (pin "2") (pinfunction "A_2") (pintype "unspecified"))
      (node (ref "SW25") (pin "2") (pinfunction "2_2") (pintype "unspecified"))
    )
    (net (code "39") (name "Net-(D26-A)") (class "Default")
      (node (ref "D26") (pin "2") (pinfunction "A_2") (pintype "unspecified"))
      (node (ref "SW26") (pin "2") (pinfunction "2_2") (pintype "unspecified"))
    )
    (net (code "40") (name "Net-(D27-A)") (class "Default")
      (node (ref "D27") (pin "2") (pinfunction "A_2") (pintype "unspecified"))
      (node (ref "SW27") (pin "2") (pinfunction "2_2") (pintype "unspecified"))
    )
    (net (code "41") (name "Net-(D28-A)") (class "Default")
      (node (ref "D28") (pin "2") (pinfunction "A_2") (pintype "unspecified"))
      (node (ref "SW28") (pin "2") (pinfunction "2_2") (pintype "unspecified"))
    )
    (net (code "42") (name "Net-(D29-A)") (class "Default")
      (node (ref "D29") (pin "2") (pinfunction "A_2") (pintype "unspecified"))
      (node (ref "SW29") (pin "2") (pinfunction "2_2") (pintype "unspecified"))
    )
    (net (code "43") (name "Net-(D30-A)") (class "Default")
      (node (ref "D30") (pin "2") (pinfunction "A_2") (pintype "unspecified"))
      (node (ref "SW30") (pin "2") (pinfunction "2_2") (pintype "unspecified"))
    )
    (net (code "44") (name "Net-(D31-A)") (class "Default")
      (node (ref "D31") (pin "2") (pinfunction "A_2") (pintype "unspecified"))
      (node (ref "SW31") (pin "2") (pinfunction "2_2") (pintype "unspecified"))
    )
    (net (code "45") (name "Net-(D32-A)") (class "Default")
      (node (ref "D32") (pin "2") (pinfunction "A_2") (pintype "unspecified"))
      (node (ref "SW32") (pin "2") (pinfunction "2_2") (pintype "unspecified"))
    )
    (net (code "46") (name "Net-(R1-Pad3)") (class "Default")
      (node (ref "R1") (pin "3") (pinfunction "3_3") (pintype "unspecified"))
      (node (ref "R10") (pin "3") (pinfunction "3_3") (pintype "unspecified"))
      (node (ref "R2") (pin "3") (pinfunction "3_3") (pintype "unspecified"))
      (node (ref "R3") (pin "3") (pinfunction "3_3") (pintype "unspecified"))
      (node (ref "R4") (pin "3") (pinfunction "3_3") (pintype "unspecified"))
      (node (ref "R5") (pin "3") (pinfunction "3_3") (pintype "unspecified"))
      (node (ref "R6") (pin "3") (pinfunction "3_3") (pintype "unspecified"))
      (node (ref "R7") (pin "3") (pinfunction "3_3") (pintype "unspecified"))
      (node (ref "R8") (pin "3") (pinfunction "3_3") (pintype "unspecified"))
      (node (ref "R9") (pin "3") (pinfunction "3_3") (pintype "unspecified"))
      (node (ref "U1") (pin "27") (pinfunction "3V3_27") (pintype "input"))
    )
    (net (code "47") (name "Net-(U1-16(A2)-SCL1-RX4)") (class "Default")
      (node (ref "C3") (pin "2") (pinfunction "2_2") (pintype "input"))
      (node (ref "R3") (pin "2") (pinfunction "2_2") (pintype "unspecified"))
      (node (ref "U1") (pin "35") (pinfunction "16(A2)-SCL1-RX4_35") (pintype "input"))
    )
    (net (code "48") (name "Net-(U1-17(A3)-SDA1-TX4)") (class "Default")
      (node (ref "C4") (pin "2") (pinfunction "2_2") (pintype "input"))
      (node (ref "R4") (pin "2") (pinfunction "2_2") (pintype "unspecified"))
      (node (ref "U1") (pin "34") (pinfunction "17(A3)-SDA1-TX4_34") (pintype "input"))
    )
    (net (code "49") (name "Net-(U1-18(A4)-SDA)") (class "Default")
      (node (ref "C5") (pin "2") (pinfunction "2_2") (pintype "input"))
      (node (ref "R5") (pin "2") (pinfunction "2_2") (pintype "unspecified"))
      (node (ref "U1") (pin "33") (pinfunction "18(A4)-SDA_33") (pintype "input"))
    )
    (net (code "50") (name "Net-(U1-19(A5)-SCL)") (class "Default")
      (node (ref "C6") (pin "1") (pinfunction "1_1") (pintype "input"))
      (node (ref "R6") (pin "2") (pinfunction "2_2") (pintype "unspecified"))
      (node (ref "U1") (pin "32") (pinfunction "19(A5)-SCL_32") (pintype "input"))
    )
    (net (code "51") (name "Net-(U1-20(A6)-TX5)") (class "Default")
      (node (ref "C7") (pin "2") (pinfunction "2_2") (pintype "input"))
      (node (ref "R7") (pin "2") (pinfunction "2_2") (pintype "unspecified"))
      (node (ref "U1") (pin "31") (pinfunction "20(A6)-TX5_31") (pintype "input"))
    )
    (net (code "52") (name "Net-(U1-21(A7)-RX5)") (class "Default")
      (node (ref "C8") (pin "2") (pinfunction "2_2") (pintype "input"))
      (node (ref "R8") (pin "2") (pinfunction "2_2") (pintype "unspecified"))
      (node (ref "U1") (pin "30") (pinfunction "21(A7)-RX5_30") (pintype "input"))
    )
    (net (code "53") (name "Net-(U1-22(A8))") (class "Default")
      (node (ref "C9") (pin "2") (pinfunction "2_2") (pintype "input"))
      (node (ref "R9") (pin "2") (pinfunction "2_2") (pintype "unspecified"))
      (node (ref "U1") (pin "29") (pinfunction "22(A8)_29") (pintype "input"))
    )
    (net (code "54") (name "Net-(U1-23(A9))") (class "Default")
      (node (ref "C10") (pin "2") (pinfunction "2_2") (pintype "input"))
      (node (ref "R10") (pin "2") (pinfunction "2_2") (pintype "unspecified"))
      (node (ref "U1") (pin "28") (pinfunction "23(A9)_28") (pintype "input"))
    )
    (net (code "55") (name "Net-(U1-38(A14))") (class "Default")
      (node (ref "C1") (pin "1") (pinfunction "1_1") (pintype "input"))
      (node (ref "R1") (pin "2") (pinfunction "2_2") (pintype "unspecified"))
      (node (ref "U1") (pin "43") (pinfunction "38(A14)_43") (pintype "input"))
    )
    (net (code "56") (name "Net-(U1-39(A15))") (class "Default")
      (node (ref "C2") (pin "2") (pinfunction "2_2") (pintype "input"))
      (node (ref "R2") (pin "2") (pinfunction "2_2") (pintype "unspecified"))
      (node (ref "U1") (pin "42") (pinfunction "39(A15)_42") (pintype "input"))
    )
    (net (code "57") (name "unconnected-(C2-Pad1)") (class "Default")
      (node (ref "C2") (pin "1") (pinfunction "1_1") (pintype "input"))
    )
    (net (code "58") (name "unconnected-(R1-Pad4)") (class "Default")
      (node (ref "R1") (pin "4") (pinfunction "4_4") (pintype "unspecified"))
    )
    (net (code "59") (name "unconnected-(R1-Pad5)") (class "Default")
      (node (ref "R1") (pin "5") (pinfunction "5_5") (pintype "unspecified"))
    )
    (net (code "60") (name "unconnected-(R1-Pad6)") (class "Default")
      (node (ref "R1") (pin "6") (pinfunction "6_6") (pintype "unspecified"))
    )
    (net (code "61") (name "unconnected-(R1-Pad7)") (class "Default")
      (node (ref "R1") (pin "7") (pinfunction "7_7") (pintype "unspecified"))
    )
    (net (code "62") (name "unconnected-(R2-Pad1)") (class "Default")
      (node (ref "R2") (pin "1") (pinfunction "1_1") (pintype "unspecified"))
    )
    (net (code "63") (name "unconnected-(R2-Pad4)") (class "Default")
      (node (ref "R2") (pin "4") (pinfunction "4_4") (pintype "unspecified"))
    )
    (net (code "64") (name "unconnected-(R2-Pad5)") (class "Default")
      (node (ref "R2") (pin "5") (pinfunction "5_5") (pintype "unspecified"))
    )
    (net (code "65") (name "unconnected-(R2-Pad6)") (class "Default")
      (node (ref "R2") (pin "6") (pinfunction "6_6") (pintype "unspecified"))
    )
    (net (code "66") (name "unconnected-(R2-Pad7)") (class "Default")
      (node (ref "R2") (pin "7") (pinfunction "7_7") (pintype "unspecified"))
    )
    (net (code "67") (name "unconnected-(R3-Pad4)") (class "Default")
      (node (ref "R3") (pin "4") (pinfunction "4_4") (pintype "unspecified"))
    )
    (net (code "68") (name "unconnected-(R3-Pad5)") (class "Default")
      (node (ref "R3") (pin "5") (pinfunction "5_5") (pintype "unspecified"))
    )
    (net (code "69") (name "unconnected-(R3-Pad6)") (class "Default")
      (node (ref "R3") (pin "6") (pinfunction "6_6") (pintype "unspecified"))
    )
    (net (code "70") (name "unconnected-(R3-Pad7)") (class "Default")
      (node (ref "R3") (pin "7") (pinfunction "7_7") (pintype "unspecified"))
    )
    (net (code "71") (name "unconnected-(R4-Pad4)") (class "Default")
      (node (ref "R4") (pin "4") (pinfunction "4_4") (pintype "unspecified"))
    )
    (net (code "72") (name "unconnected-(R4-Pad5)") (class "Default")
      (node (ref "R4") (pin "5") (pinfunction "5_5") (pintype "unspecified"))
    )
    (net (code "73") (name "unconnected-(R4-Pad6)") (class "Default")
      (node (ref "R4") (pin "6") (pinfunction "6_6") (pintype "unspecified"))
    )
    (net (code "74") (name "unconnected-(R4-Pad7)") (class "Default")
      (node (ref "R4") (pin "7") (pinfunction "7_7") (pintype "unspecified"))
    )
    (net (code "75") (name "unconnected-(R5-Pad4)") (class "Default")
      (node (ref "R5") (pin "4") (pinfunction "4_4") (pintype "unspecified"))
    )
    (net (code "76") (name "unconnected-(R5-Pad5)") (class "Default")
      (node (ref "R5") (pin "5") (pinfunction "5_5") (pintype "unspecified"))
    )
    (net (code "77") (name "unconnected-(R5-Pad6)") (class "Default")
      (node (ref "R5") (pin "6") (pinfunction "6_6") (pintype "unspecified"))
    )
    (net (code "78") (name "unconnected-(R5-Pad7)") (class "Default")
      (node (ref "R5") (pin "7") (pinfunction "7_7") (pintype "unspecified"))
    )
    (net (code "79") (name "unconnected-(R6-Pad4)") (class "Default")
      (node (ref "R6") (pin "4") (pinfunction "4_4") (pintype "unspecified"))
    )
    (net (code "80") (name "unconnected-(R6-Pad5)") (class "Default")
      (node (ref "R6") (pin "5") (pinfunction "5_5") (pintype "unspecified"))
    )
    (net (code "81") (name "unconnected-(R6-Pad6)") (class "Default")
      (node (ref "R6") (pin "6") (pinfunction "6_6") (pintype "unspecified"))
    )
    (net (code "82") (name "unconnected-(R6-Pad7)") (class "Default")
      (node (ref "R6") (pin "7") (pinfunction "7_7") (pintype "unspecified"))
    )
    (net (code "83") (name "unconnected-(R7-Pad4)") (class "Default")
      (node (ref "R7") (pin "4") (pinfunction "4_4") (pintype "unspecified"))
    )
    (net (code "84") (name "unconnected-(R7-Pad5)") (class "Default")
      (node (ref "R7") (pin "5") (pinfunction "5_5") (pintype "unspecified"))
    )
    (net (code "85") (name "unconnected-(R7-Pad6)") (class "Default")
      (node (ref "R7") (pin "6") (pinfunction "6_6") (pintype "unspecified"))
    )
    (net (code "86") (name "unconnected-(R7-Pad7)") (class "Default")
      (node (ref "R7") (pin "7") (pinfunction "7_7") (pintype "unspecified"))
    )
    (net (code "87") (name "unconnected-(R8-Pad4)") (class "Default")
      (node (ref "R8") (pin "4") (pinfunction "4_4") (pintype "unspecified"))
    )
    (net (code "88") (name "unconnected-(R8-Pad5)") (class "Default")
      (node (ref "R8") (pin "5") (pinfunction "5_5") (pintype "unspecified"))
    )
    (net (code "89") (name "unconnected-(R8-Pad6)") (class "Default")
      (node (ref "R8") (pin "6") (pinfunction "6_6") (pintype "unspecified"))
    )
    (net (code "90") (name "unconnected-(R8-Pad7)") (class "Default")
      (node (ref "R8") (pin "7") (pinfunction "7_7") (pintype "unspecified"))
    )
    (net (code "91") (name "unconnected-(R9-Pad4)") (class "Default")
      (node (ref "R9") (pin "4") (pinfunction "4_4") (pintype "unspecified"))
    )
    (net (code "92") (name "unconnected-(R9-Pad5)") (class "Default")
      (node (ref "R9") (pin "5") (pinfunction "5_5") (pintype "unspecified"))
    )
    (net (code "93") (name "unconnected-(R9-Pad6)") (class "Default")
      (node (ref "R9") (pin "6") (pinfunction "6_6") (pintype "unspecified"))
    )
    (net (code "94") (name "unconnected-(R9-Pad7)") (class "Default")
      (node (ref "R9") (pin "7") (pinfunction "7_7") (pintype "unspecified"))
    )
    (net (code "95") (name "unconnected-(R10-Pad4)") (class "Default")
      (node (ref "R10") (pin "4") (pinfunction "4_4") (pintype "unspecified"))
    )
    (net (code "96") (name "unconnected-(R10-Pad5)") (class "Default")
      (node (ref "R10") (pin "5") (pinfunction "5_5") (pintype "unspecified"))
    )
    (net (code "97") (name "unconnected-(R10-Pad6)") (class "Default")
      (node (ref "R10") (pin "6") (pinfunction "6_6") (pintype "unspecified"))
    )
    (net (code "98") (name "unconnected-(R10-Pad7)") (class "Default")
      (node (ref "R10") (pin "7") (pinfunction "7_7") (pintype "unspecified"))
    )
    (net (code "99") (name "unconnected-(U1-3V3-Pad15)") (class "Default")
      (node (ref "U1") (pin "15") (pinfunction "3V3_15") (pintype "input"))
    )
    (net (code "100") (name "unconnected-(U1-6-Pad8)") (class "Default")
      (node (ref "U1") (pin "8") (pinfunction "6_8") (pintype "input"))
    )
    (net (code "101") (name "unconnected-(U1-10-Pad12)") (class "Default")
      (node (ref "U1") (pin "12") (pinfunction "10_12") (pintype "input"))
    )
    (net (code "102") (name "unconnected-(U1-11-MOSI-Pad13)") (class "Default")
      (node (ref "U1") (pin "13") (pinfunction "11-MOSI_13") (pintype "input"))
    )
    (net (code "103") (name "unconnected-(U1-12-MISO-Pad14)") (class "Default")
      (node (ref "U1") (pin "14") (pinfunction "12-MISO_14") (pintype "input"))
    )
    (net (code "104") (name "unconnected-(U1-13-SCK-Pad38)") (class "Default")
      (node (ref "U1") (pin "38") (pinfunction "13-SCK_38") (pintype "input"))
    )
    (net (code "105") (name "unconnected-(U1-14(A0)-TX3-Pad37)") (class "Default")
      (node (ref "U1") (pin "37") (pinfunction "14(A0)-TX3_37") (pintype "input"))
    )
    (net (code "106") (name "unconnected-(U1-15(A1)-RX3-Pad36)") (class "Default")
      (node (ref "U1") (pin "36") (pinfunction "15(A1)-RX3_36") (pintype "input"))
    )
    (net (code "107") (name "unconnected-(U1-24(A10)-SCL2-TX6-Pad16)") (class "Default")
      (node (ref "U1") (pin "16") (pinfunction "24(A10)-SCL2-TX6_16") (pintype "input"))
    )
    (net (code "108") (name "unconnected-(U1-25(A11)-SDA2-RX6-Pad17)") (class "Default")
      (node (ref "U1") (pin "17") (pinfunction "25(A11)-SDA2-RX6_17") (pintype "input"))
    )
    (net (code "109") (name "unconnected-(U1-26(A12)-MOSI1-Pad18)") (class "Default")
      (node (ref "U1") (pin "18") (pinfunction "26(A12)-MOSI1_18") (pintype "input"))
    )
    (net (code "110") (name "unconnected-(U1-27(A13)-SCK1-Pad19)") (class "Default")
      (node (ref "U1") (pin "19") (pinfunction "27(A13)-SCK1_19") (pintype "input"))
    )
    (net (code "111") (name "unconnected-(U1-28-RX7-Pad20)") (class "Default")
      (node (ref "U1") (pin "20") (pinfunction "28-RX7_20") (pintype "input"))
    )
    (net (code "112") (name "unconnected-(U1-29-TX7-Pad21)") (class "Default")
      (node (ref "U1") (pin "21") (pinfunction "29-TX7_21") (pintype "input"))
    )
    (net (code "113") (name "unconnected-(U1-33-Pad48)") (class "Default")
      (node (ref "U1") (pin "48") (pinfunction "33_48") (pintype "input"))
    )
    (net (code "114") (name "unconnected-(U1-34-RX8-Pad47)") (class "Default")
      (node (ref "U1") (pin "47") (pinfunction "34-RX8_47") (pintype "input"))
    )
    (net (code "115") (name "unconnected-(U1-35-TX8-Pad46)") (class "Default")
      (node (ref "U1") (pin "46") (pinfunction "35-TX8_46") (pintype "input"))
    )
    (net (code "116") (name "unconnected-(U1-36-Pad45)") (class "Default")
      (node (ref "U1") (pin "45") (pinfunction "36_45") (pintype "input"))
    )
    (net (code "117") (name "unconnected-(U1-37-Pad44)") (class "Default")
      (node (ref "U1") (pin "44") (pinfunction "37_44") (pintype "input"))
    )
    (net (code "118") (name "unconnected-(U1-40(A16)-Pad41)") (class "Default")
      (node (ref "U1") (pin "41") (pinfunction "40(A16)_41") (pintype "input"))
    )
    (net (code "119") (name "unconnected-(U1-41(A17)-Pad40)") (class "Default")
      (node (ref "U1") (pin "40") (pinfunction "41(A17)_40") (pintype "input"))
    )
    (net (code "120") (name "unconnected-(U1-VIN-Pad25)") (class "Default")
      (node (ref "U1") (pin "25") (pinfunction "VIN_25") (pintype "input"))
    )
  )
)
